# led_daughter_new_led.net
KiCad netlist of a schematic drawn in EAGLE
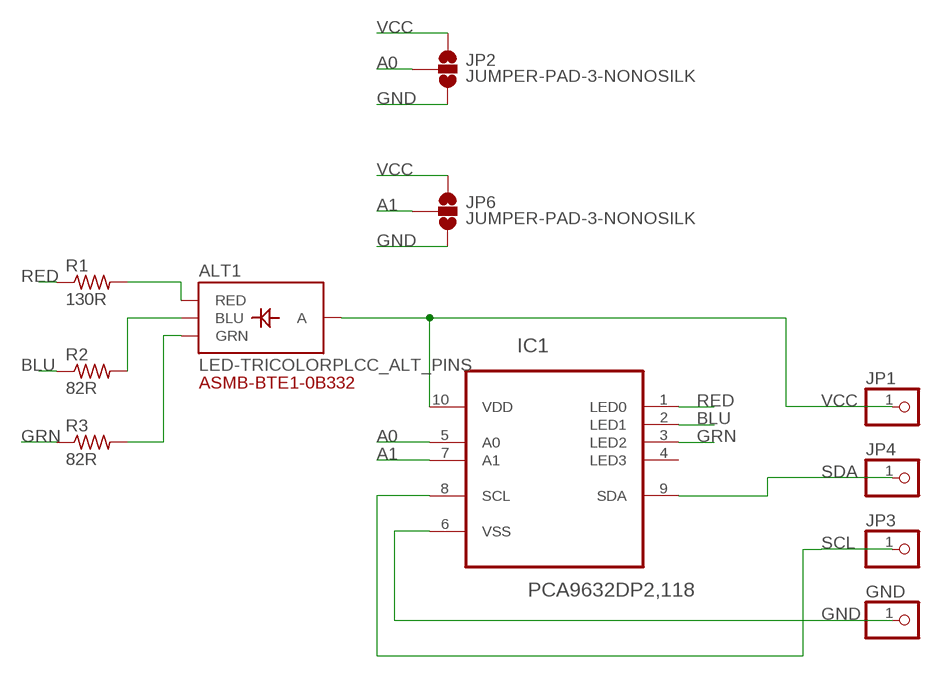
[diagram p0: schematic, sheet 1]

(export (version "E")
  (design (tool "Eeschema 10.0.6"))
  (components
    (comp (ref "ALT1")
      (value "LED-TRICOLORPLCC_ALT_PINS")
      (footprint "eagle-import:LED-TRICOLOR-PLCC")
      (libsource (lib "eagle-import") (part "LED-TRICOLORPLCC_ALT_PINS"))
    )
    (comp (ref "GND")
      (value "PINHD-1X1CB")
      (footprint "eagle-import:1X01-CLEANBIG")
      (libsource (lib "eagle-import") (part "PINHD-1X1CB"))
    )
    (comp (ref "IC1")
      (value "PCA9632DP2,118")
      (footprint "eagle-import:SOP50P490X110-10N")
      (libsource (lib "eagle-import") (part "PCA9632DP2,118"))
    )
    (comp (ref "JP1")
      (value "PINHD-1X1CB")
      (footprint "eagle-import:1X01-CLEANBIG")
      (libsource (lib "eagle-import") (part "PINHD-1X1CB"))
    )
    (comp (ref "JP2")
      (value "JUMPER-PAD-3-NONOSILK")
      (footprint "eagle-import:PAD-JUMPER-3-NO_NO_SILK")
      (libsource (lib "eagle-import") (part "JUMPER-PAD-3-NONOSILK"))
    )
    (comp (ref "JP3")
      (value "PINHD-1X1CB")
      (footprint "eagle-import:1X01-CLEANBIG")
      (libsource (lib "eagle-import") (part "PINHD-1X1CB"))
    )
    (comp (ref "JP4")
      (value "PINHD-1X1CB")
      (footprint "eagle-import:1X01-CLEANBIG")
      (libsource (lib "eagle-import") (part "PINHD-1X1CB"))
    )
    (comp (ref "JP6")
      (value "JUMPER-PAD-3-NONOSILK")
      (footprint "eagle-import:PAD-JUMPER-3-NO_NO_SILK")
      (libsource (lib "eagle-import") (part "JUMPER-PAD-3-NONOSILK"))
    )
    (comp (ref "R1")
      (value "130R")
      (footprint "eagle-import:R0603")
      (libsource (lib "eagle-import") (part "R-US_R0603"))
    )
    (comp (ref "R2")
      (value "82R")
      (footprint "eagle-import:R0603")
      (libsource (lib "eagle-import") (part "R-US_R0603"))
    )
    (comp (ref "R3")
      (value "82R")
      (footprint "eagle-import:R0603")
      (libsource (lib "eagle-import") (part "R-US_R0603"))
    )
  )
  (nets
    (net (code "1") (name "/A0") (class "Default")
      (node (ref "IC1") (pin "5") (pinfunction "A0_5") (pintype "input"))
      (node (ref "JP2") (pin "2") (pinfunction "2_2") (pintype "passive"))
    )
    (net (code "2") (name "/A1") (class "Default")
      (node (ref "IC1") (pin "7") (pinfunction "A1_7") (pintype "input"))
      (node (ref "JP6") (pin "2") (pinfunction "2_2") (pintype "passive"))
    )
    (net (code "3") (name "/BLU") (class "Default")
      (node (ref "IC1") (pin "2") (pinfunction "LED1_2") (pintype "output"))
      (node (ref "R2") (pin "1") (pinfunction "1_1") (pintype "passive"))
    )
    (net (code "4") (name "/GND") (class "Default")
      (node (ref "GND") (pin "1") (pinfunction "1_1") (pintype "passive"))
      (node (ref "IC1") (pin "6") (pinfunction "VSS_6") (pintype "power_in"))
      (node (ref "JP2") (pin "3") (pinfunction "3_3") (pintype "passive"))
      (node (ref "JP6") (pin "3") (pinfunction "3_3") (pintype "passive"))
    )
    (net (code "5") (name "/GRN") (class "Default")
      (node (ref "IC1") (pin "3") (pinfunction "LED2_3") (pintype "output"))
      (node (ref "R3") (pin "1") (pinfunction "1_1") (pintype "passive"))
    )
    (net (code "6") (name "/RED") (class "Default")
      (node (ref "IC1") (pin "1") (pinfunction "LED0_1") (pintype "output"))
      (node (ref "R1") (pin "1") (pinfunction "1_1") (pintype "passive"))
    )
    (net (code "7") (name "/SCL") (class "Default")
      (node (ref "IC1") (pin "8") (pinfunction "SCL_8") (pintype "input"))
      (node (ref "JP3") (pin "1") (pinfunction "1_1") (pintype "passive"))
    )
    (net (code "8") (name "/SDA") (class "Default")
      (node (ref "IC1") (pin "9") (pinfunction "SDA_9") (pintype "bidirectional"))
      (node (ref "JP4") (pin "1") (pinfunction "1_1") (pintype "passive"))
    )
    (net (code "9") (name "/VCC") (class "Default")
      (node (ref "ALT1") (pin "PAD2") (pinfunction "A_PAD2") (pintype "bidirectional"))
      (node (ref "IC1") (pin "10") (pinfunction "VDD_10") (pintype "power_in"))
      (node (ref "JP1") (pin "1") (pinfunction "1_1") (pintype "passive"))
      (node (ref "JP2") (pin "1") (pinfunction "1_1") (pintype "passive"))
      (node (ref "JP6") (pin "1") (pinfunction "1_1") (pintype "passive"))
    )
    (net (code "10") (name "Net-(ALT1-BLU)") (class "Default")
      (node (ref "ALT1") (pin "PAD1") (pinfunction "BLU_PAD1") (pintype "bidirectional"))
      (node (ref "R2") (pin "2") (pinfunction "2_2") (pintype "passive"))
    )
    (net (code "11") (name "Net-(ALT1-GRN)") (class "Default")
      (node (ref "ALT1") (pin "PAD4") (pinfunction "GRN_PAD4") (pintype "bidirectional"))
      (node (ref "R3") (pin "2") (pinfunction "2_2") (pintype "passive"))
    )
    (net (code "12") (name "Net-(ALT1-RED)") (class "Default")
      (node (ref "ALT1") (pin "PAD3") (pinfunction "RED_PAD3") (pintype "bidirectional"))
      (node (ref "R1") (pin "2") (pinfunction "2_2") (pintype "passive"))
    )
    (net (code "13") (name "unconnected-(IC1-LED3-Pad4)") (class "Default")
      (node (ref "IC1") (pin "4") (pinfunction "LED3_4") (pintype "output"))
    )
  )
)
